# PCB-RS422-DB9-BO.net
KiCad netlist of a schematic drawn in EAGLE
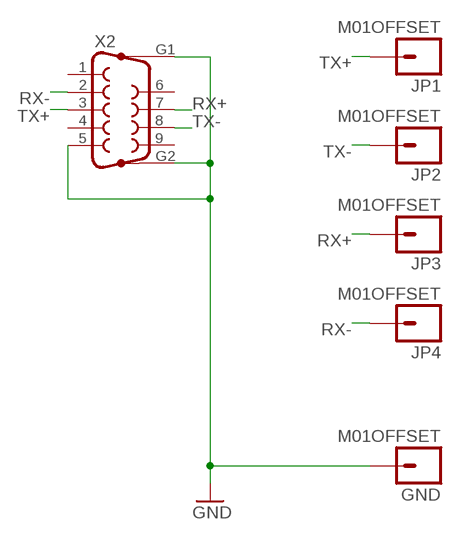
[diagram p0: schematic, sheet 1]

(export (version "E")
  (design (tool "Eeschema 10.0.6"))
  (components
    (comp (ref "GND")
      (value "M01OFFSET")
      (footprint "eagle-import:1X01_OFFSET")
      (libsource (lib "eagle-import") (part "M01OFFSET"))
    )
    (comp (ref "JP1")
      (value "M01OFFSET")
      (footprint "eagle-import:1X01_OFFSET")
      (libsource (lib "eagle-import") (part "M01OFFSET"))
    )
    (comp (ref "JP2")
      (value "M01OFFSET")
      (footprint "eagle-import:1X01_OFFSET")
      (libsource (lib "eagle-import") (part "M01OFFSET"))
    )
    (comp (ref "JP3")
      (value "M01OFFSET")
      (footprint "eagle-import:1X01_OFFSET")
      (libsource (lib "eagle-import") (part "M01OFFSET"))
    )
    (comp (ref "JP4")
      (value "M01OFFSET")
      (footprint "eagle-import:1X01_OFFSET")
      (libsource (lib "eagle-import") (part "M01OFFSET"))
    )
    (comp (ref "X2")
      (value "F09HP")
      (footprint "eagle-import:F09HP")
      (libsource (lib "eagle-import") (part "F09HP"))
    )
  )
  (nets
    (net (code "1") (name "GND") (class "Default")
      (node (ref "GND") (pin "1") (pinfunction "1_1") (pintype "passive"))
      (node (ref "X2") (pin "5") (pinfunction "5_5") (pintype "passive"))
      (node (ref "X2") (pin "G1") (pinfunction "G1_G1") (pintype "passive"))
      (node (ref "X2") (pin "G2") (pinfunction "G2_G2") (pintype "passive"))
    )
    (net (code "2") (name "RX+") (class "Default")
      (node (ref "JP3") (pin "1") (pinfunction "1_1") (pintype "passive"))
      (node (ref "X2") (pin "7") (pinfunction "7_7") (pintype "passive"))
    )
    (net (code "3") (name "RX-") (class "Default")
      (node (ref "JP4") (pin "1") (pinfunction "1_1") (pintype "passive"))
      (node (ref "X2") (pin "2") (pinfunction "2_2") (pintype "passive"))
    )
    (net (code "4") (name "TX+") (class "Default")
      (node (ref "JP1") (pin "1") (pinfunction "1_1") (pintype "passive"))
      (node (ref "X2") (pin "3") (pinfunction "3_3") (pintype "passive"))
    )
    (net (code "5") (name "TX-") (class "Default")
      (node (ref "JP2") (pin "1") (pinfunction "1_1") (pintype "passive"))
      (node (ref "X2") (pin "8") (pinfunction "8_8") (pintype "passive"))
    )
    (net (code "6") (name "unconnected-(X2-Pad1)") (class "Default")
      (node (ref "X2") (pin "1") (pinfunction "1_1") (pintype "passive"))
    )
    (net (code "7") (name "unconnected-(X2-Pad4)") (class "Default")
      (node (ref "X2") (pin "4") (pinfunction "4_4") (pintype "passive"))
    )
    (net (code "8") (name "unconnected-(X2-Pad6)") (class "Default")
      (node (ref "X2") (pin "6") (pinfunction "6_6") (pintype "passive"))
    )
    (net (code "9") (name "unconnected-(X2-Pad9)") (class "Default")
      (node (ref "X2") (pin "9") (pinfunction "9_9") (pintype "passive"))
    )
  )
)
